# Barometer.net
KiCad netlist of a schematic drawn in Altium Designer
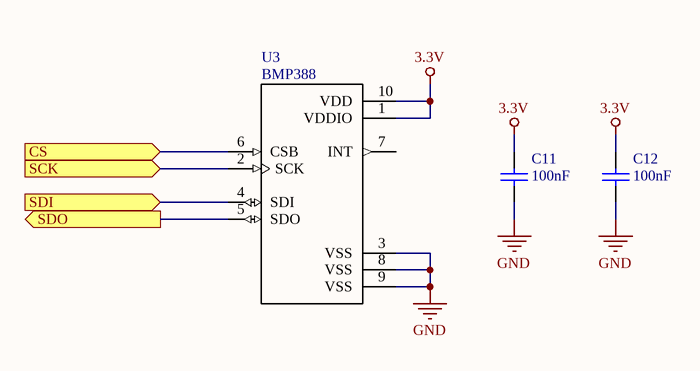
[diagram p0: Barometer.SchDoc]

(export (version "E")
  (design (tool "Eeschema 10.0.6"))
  (components
    (comp (ref "C11")
      (value "100nF")
      (footprint "0603 to 0805 SMD")
      (fields (field (name "Comment") "Cap"))
      (libsource (lib "RC0805FR-0751K1L") (part "Cap"))
    )
    (comp (ref "C12")
      (value "100nF")
      (footprint "0603 to 0805 SMD")
      (fields (field (name "Comment") "Cap"))
      (libsource (lib "RC0805FR-0751K1L") (part "Cap"))
    )
    (comp (ref "U3")
      (value "BMP388")
      (footprint "PQFN50P200X200X80-10N")
      (description "P-Sensor SPI I2C 1, 25 Bar SMD")
      (fields (field (name "MF") "Bosch Sensortec"))
      (libsource (lib "BMP388") (part "BMP388"))
    )
  )
  (nets
    (net (code "1") (name "/CS") (class "Default")
      (node (ref "U3") (pin "6") (pinfunction "CSB_6") (pintype "input"))
    )
    (net (code "2") (name "/SCK") (class "Default")
      (node (ref "U3") (pin "2") (pinfunction "SCK_2") (pintype "input"))
    )
    (net (code "3") (name "/SDI") (class "Default")
      (node (ref "U3") (pin "4") (pinfunction "SDI_4") (pintype "bidirectional"))
    )
    (net (code "4") (name "/SDO") (class "Default")
      (node (ref "U3") (pin "5") (pinfunction "SDO_5") (pintype "bidirectional"))
    )
    (net (code "5") (name "3.3V") (class "Default")
      (node (ref "C11") (pin "2") (pinfunction "2_2") (pintype "passive"))
      (node (ref "C12") (pin "2") (pinfunction "2_2") (pintype "passive"))
      (node (ref "U3") (pin "1") (pinfunction "VDDIO_1") (pintype "power_in"))
      (node (ref "U3") (pin "10") (pinfunction "VDD_10") (pintype "power_in"))
    )
    (net (code "6") (name "GND") (class "Default")
      (node (ref "C11") (pin "1") (pinfunction "1_1") (pintype "passive"))
      (node (ref "C12") (pin "1") (pinfunction "1_1") (pintype "passive"))
      (node (ref "U3") (pin "3") (pinfunction "VSS_3") (pintype "power_in"))
      (node (ref "U3") (pin "8") (pinfunction "VSS_8") (pintype "power_in"))
      (node (ref "U3") (pin "9") (pinfunction "VSS_9") (pintype "power_in"))
    )
    (net (code "7") (name "unconnected-(U3-INT-Pad7)") (class "Default")
      (node (ref "U3") (pin "7") (pinfunction "INT_7") (pintype "output"))
    )
  )
)
